# stm_board_f407_1_2_4.net
KiCad netlist of a schematic drawn in EAGLE
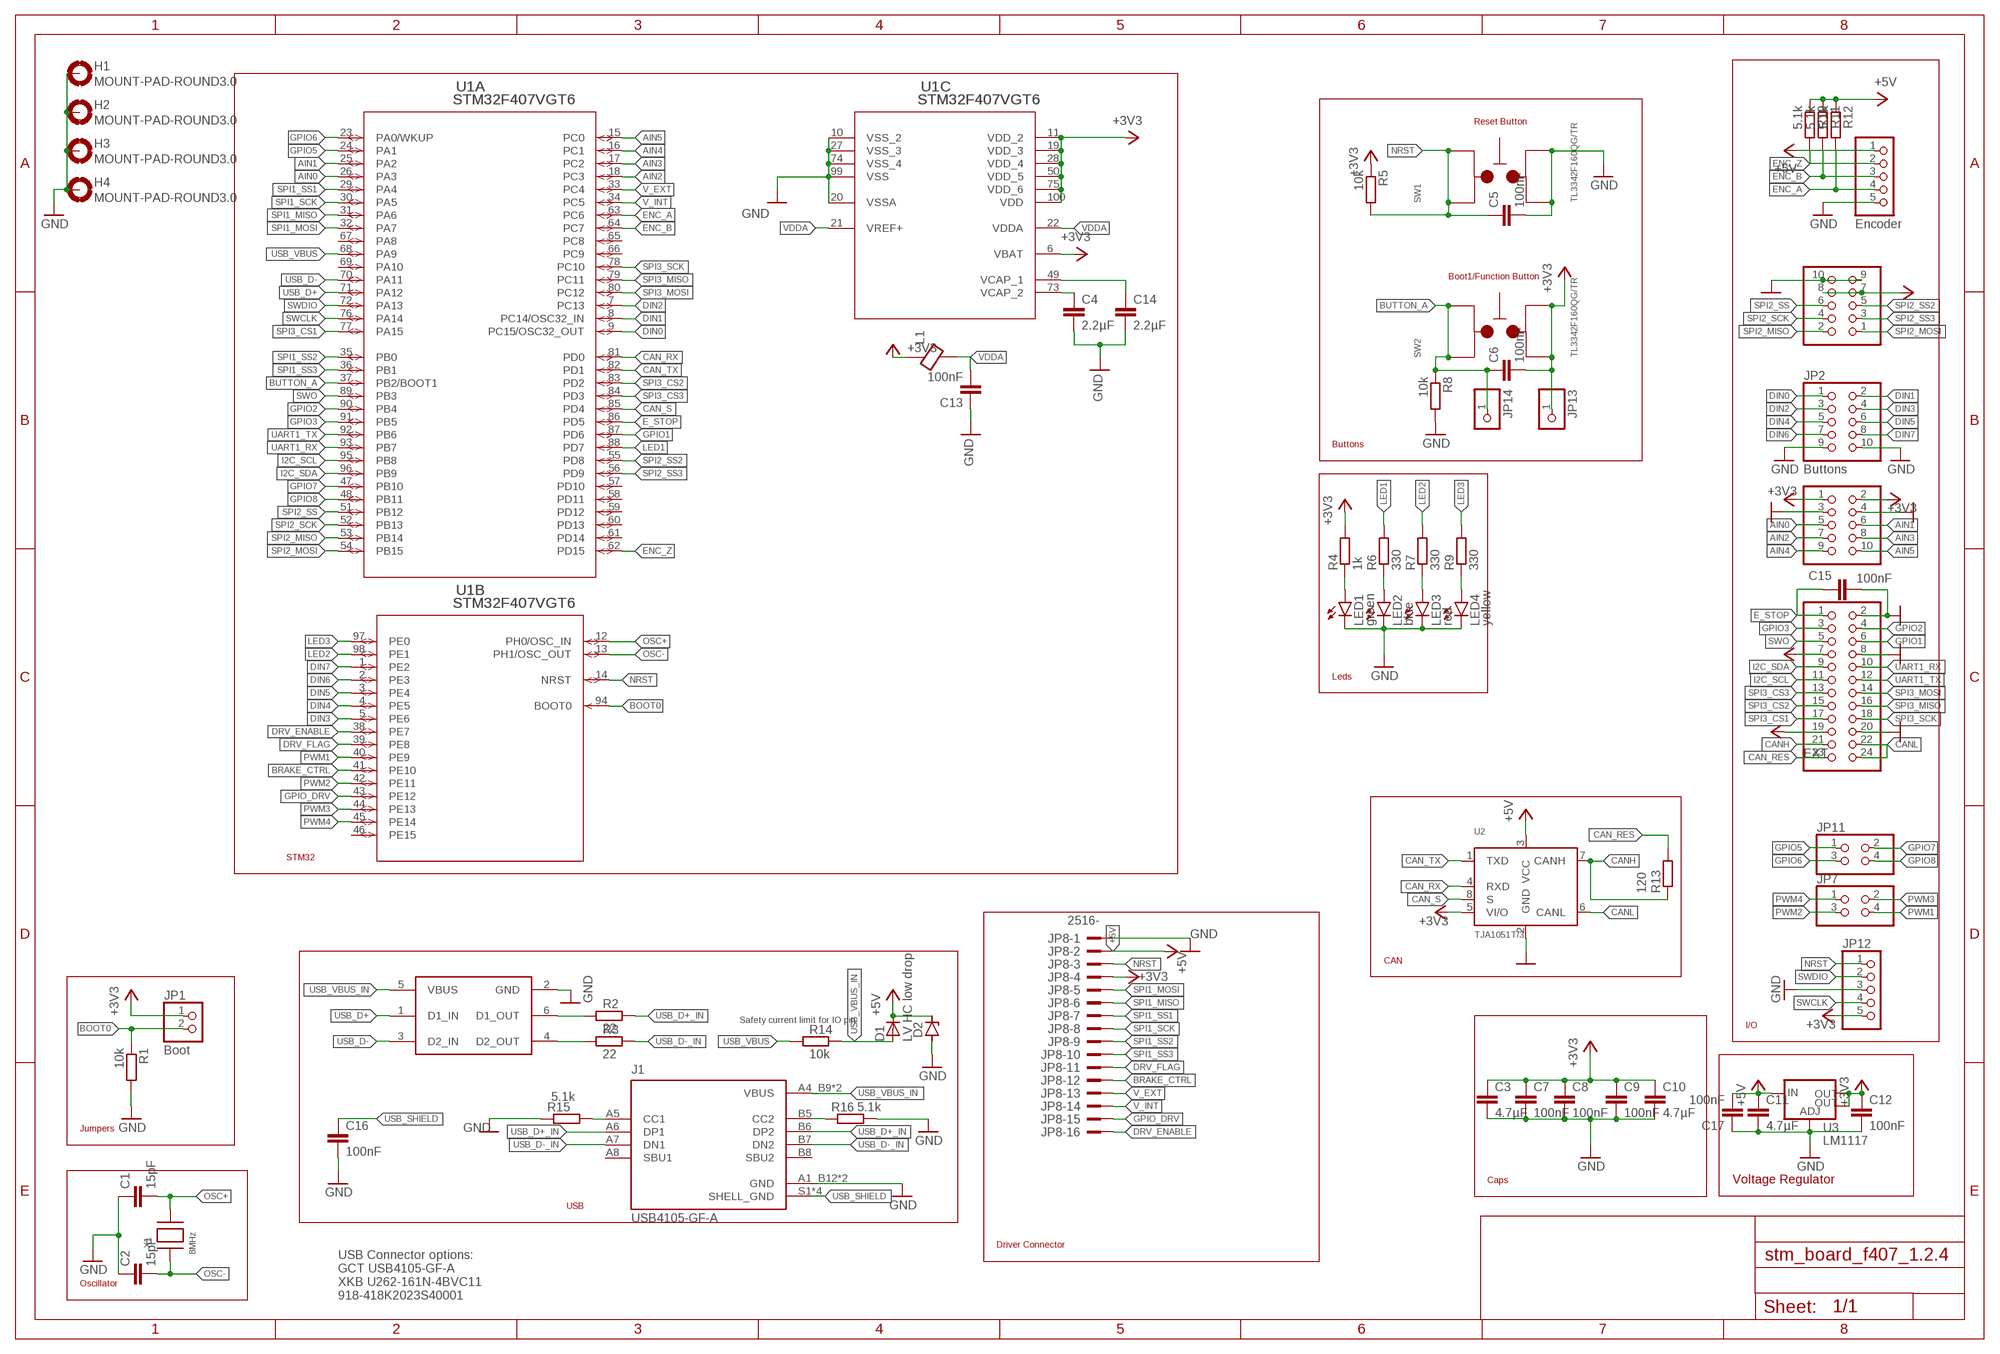
[diagram p0: schematic, sheet 1]

(export (version "E")
  (design (tool "Eeschema 10.0.6"))
  (components
    (comp (ref "C1")
      (value "15pF")
      (footprint "eagle-import:C0603")
      (libsource (lib "eagle-import") (part "C-EUC0603"))
    )
    (comp (ref "C2")
      (value "15pF")
      (footprint "eagle-import:C0603")
      (libsource (lib "eagle-import") (part "C-EUC0603"))
    )
    (comp (ref "C3")
      (value "4.7µF")
      (footprint "eagle-import:C0805")
      (libsource (lib "eagle-import") (part "C-EUC0805"))
    )
    (comp (ref "C4")
      (value "2.2µF")
      (footprint "eagle-import:C0603")
      (libsource (lib "eagle-import") (part "C-EUC0603"))
    )
    (comp (ref "C5")
      (value "100nF")
      (footprint "eagle-import:C0603")
      (libsource (lib "eagle-import") (part "C-EUC0603"))
    )
    (comp (ref "C6")
      (value "100nF")
      (footprint "eagle-import:C0603")
      (libsource (lib "eagle-import") (part "C-EUC0603"))
    )
    (comp (ref "C7")
      (value "100nF")
      (footprint "eagle-import:C0603")
      (libsource (lib "eagle-import") (part "C-EUC0603"))
    )
    (comp (ref "C8")
      (value "100nF")
      (footprint "eagle-import:C0603")
      (libsource (lib "eagle-import") (part "C-EUC0603"))
    )
    (comp (ref "C9")
      (value "100nF")
      (footprint "eagle-import:C0603")
      (libsource (lib "eagle-import") (part "C-EUC0603"))
    )
    (comp (ref "C10")
      (value "4.7µF")
      (footprint "eagle-import:C0805")
      (libsource (lib "eagle-import") (part "C-EUC0805"))
    )
    (comp (ref "C11")
      (value "4.7µF")
      (footprint "eagle-import:C0805")
      (libsource (lib "eagle-import") (part "C-EUC0805"))
    )
    (comp (ref "C12")
      (value "100nF")
      (footprint "eagle-import:C0603")
      (libsource (lib "eagle-import") (part "C-EUC0603"))
    )
    (comp (ref "C13")
      (value "100nF")
      (footprint "eagle-import:C0603")
      (libsource (lib "eagle-import") (part "C-EUC0603"))
    )
    (comp (ref "C14")
      (value "2.2µF")
      (footprint "eagle-import:C0603")
      (libsource (lib "eagle-import") (part "C-EUC0603"))
    )
    (comp (ref "C15")
      (value "100nF")
      (footprint "eagle-import:C0603")
      (libsource (lib "eagle-import") (part "C-EUC0603"))
    )
    (comp (ref "C16")
      (value "100nF")
      (footprint "eagle-import:C0603")
      (libsource (lib "eagle-import") (part "C-EUC0603"))
    )
    (comp (ref "C17")
      (value "100nF")
      (footprint "eagle-import:C0603")
      (libsource (lib "eagle-import") (part "C-EUC0603"))
    )
    (comp (ref "D1")
      (value "LV HC low drop")
      (footprint "eagle-import:SMADIODE")
      (libsource (lib "eagle-import") (part "DIODESMA"))
    )
    (comp (ref "D2")
      (value "ZENER-DIODESOD80C")
      (footprint "eagle-import:SOD80C")
      (libsource (lib "eagle-import") (part "ZENER-DIODESOD80C"))
    )
    (comp (ref "H1")
      (value "MOUNT-PAD-ROUND3.0")
      (footprint "eagle-import:3,0-PAD")
      (libsource (lib "eagle-import") (part "MOUNT-PAD-ROUND3.0"))
    )
    (comp (ref "H2")
      (value "MOUNT-PAD-ROUND3.0")
      (footprint "eagle-import:3,0-PAD")
      (libsource (lib "eagle-import") (part "MOUNT-PAD-ROUND3.0"))
    )
    (comp (ref "H3")
      (value "MOUNT-PAD-ROUND3.0")
      (footprint "eagle-import:3,0-PAD")
      (libsource (lib "eagle-import") (part "MOUNT-PAD-ROUND3.0"))
    )
    (comp (ref "H4")
      (value "MOUNT-PAD-ROUND3.0")
      (footprint "eagle-import:3,0-PAD")
      (libsource (lib "eagle-import") (part "MOUNT-PAD-ROUND3.0"))
    )
    (comp (ref "J1")
      (value "USB4105-GF-A")
      (footprint "eagle-import:GCT_USB4105-GF-A")
      (fields (field (name "MF") "GCT"))
      (libsource (lib "eagle-import") (part "USB4105-GF-A"))
    )
    (comp (ref "JP1")
      (value "Boot")
      (footprint "eagle-import:1X02")
      (libsource (lib "eagle-import") (part "PINHD-1X2"))
    )
    (comp (ref "JP2")
      (value "Buttons")
      (footprint "eagle-import:2X05")
      (libsource (lib "eagle-import") (part "PINHD-2X5"))
    )
    (comp (ref "JP3")
      (value "Analog")
      (footprint "eagle-import:2X05")
      (libsource (lib "eagle-import") (part "PINHD-2X5"))
    )
    (comp (ref "JP4")
      (value "EXT")
      (footprint "eagle-import:2X12")
      (libsource (lib "eagle-import") (part "PINHD-2X12"))
    )
    (comp (ref "JP5")
      (value "Encoder")
      (footprint "eagle-import:1X05")
      (libsource (lib "eagle-import") (part "PINHD-1X5"))
    )
    (comp (ref "JP6")
      (value "SPI")
      (footprint "eagle-import:2X05")
      (libsource (lib "eagle-import") (part "PINHD-2X5"))
    )
    (comp (ref "JP7")
      (value "PINHD-2X2")
      (footprint "eagle-import:2X02")
      (libsource (lib "eagle-import") (part "PINHD-2X2"))
    )
    (comp (ref "JP8")
      (value "2516-")
      (footprint "eagle-import:PAK100_2500-16")
      (libsource (lib "eagle-import") (part "2516-"))
    )
    (comp (ref "JP11")
      (value "PINHD-2X2")
      (footprint "eagle-import:2X02")
      (libsource (lib "eagle-import") (part "PINHD-2X2"))
    )
    (comp (ref "JP12")
      (value "PINHD-1X5")
      (footprint "eagle-import:1X05")
      (libsource (lib "eagle-import") (part "PINHD-1X5"))
    )
    (comp (ref "JP13")
      (value "PINHD-1X1")
      (footprint "eagle-import:1X01")
      (libsource (lib "eagle-import") (part "PINHD-1X1"))
    )
    (comp (ref "JP14")
      (value "PINHD-1X1")
      (footprint "eagle-import:1X01")
      (libsource (lib "eagle-import") (part "PINHD-1X1"))
    )
    (comp (ref "L1")
      (value "GZ2012D601TF")
      (footprint "eagle-import:BLM21PG331SN1D")
      (fields
        (field (name "DIGIKEY_PART_NUMBER") "490-5988-2-ND")
        (field (name "MANUFACTURER") "Murata Electronics North America")
        (field (name "MPN") "BLM21PG331SN1D")
        (field (name "CREATED_BY") "PCBLayout.com")
      )
      (libsource (lib "eagle-import") (part "BLM21PG331SN1D"))
    )
    (comp (ref "LED1")
      (value "green")
      (footprint "eagle-import:SML0805")
      (libsource (lib "eagle-import") (part "LEDSML0805"))
    )
    (comp (ref "LED2")
      (value "blue")
      (footprint "eagle-import:SML0805")
      (libsource (lib "eagle-import") (part "LEDSML0805"))
    )
    (comp (ref "LED3")
      (value "red")
      (footprint "eagle-import:SML0805")
      (libsource (lib "eagle-import") (part "LEDSML0805"))
    )
    (comp (ref "LED4")
      (value "yellow")
      (footprint "eagle-import:SML0805")
      (libsource (lib "eagle-import") (part "LEDSML0805"))
    )
    (comp (ref "R1")
      (value "10k")
      (footprint "eagle-import:R0603")
      (libsource (lib "eagle-import") (part "R-EU_R0603"))
    )
    (comp (ref "R2")
      (value "22")
      (footprint "eagle-import:R0603")
      (libsource (lib "eagle-import") (part "R-EU_R0603"))
    )
    (comp (ref "R3")
      (value "22")
      (footprint "eagle-import:R0603")
      (libsource (lib "eagle-import") (part "R-EU_R0603"))
    )
    (comp (ref "R4")
      (value "1k")
      (footprint "eagle-import:R0603")
      (libsource (lib "eagle-import") (part "R-EU_R0603"))
    )
    (comp (ref "R5")
      (value "10k")
      (footprint "eagle-import:R0603")
      (libsource (lib "eagle-import") (part "R-EU_R0603"))
    )
    (comp (ref "R6")
      (value "330")
      (footprint "eagle-import:R0603")
      (libsource (lib "eagle-import") (part "R-EU_R0603"))
    )
    (comp (ref "R7")
      (value "330")
      (footprint "eagle-import:R0603")
      (libsource (lib "eagle-import") (part "R-EU_R0603"))
    )
    (comp (ref "R8")
      (value "10k")
      (footprint "eagle-import:R0603")
      (libsource (lib "eagle-import") (part "R-EU_R0603"))
    )
    (comp (ref "R9")
      (value "330")
      (footprint "eagle-import:R0603")
      (libsource (lib "eagle-import") (part "R-EU_R0603"))
    )
    (comp (ref "R10")
      (value "5.1k")
      (footprint "eagle-import:R0603")
      (libsource (lib "eagle-import") (part "R-EU_R0603"))
    )
    (comp (ref "R11")
      (value "5.1k")
      (footprint "eagle-import:R0603")
      (libsource (lib "eagle-import") (part "R-EU_R0603"))
    )
    (comp (ref "R12")
      (value "5.1k")
      (footprint "eagle-import:R0603")
      (libsource (lib "eagle-import") (part "R-EU_R0603"))
    )
    (comp (ref "R13")
      (value "120")
      (footprint "eagle-import:R0603")
      (libsource (lib "eagle-import") (part "R-EU_R0603"))
    )
    (comp (ref "R14")
      (value "10k")
      (footprint "eagle-import:R0603")
      (libsource (lib "eagle-import") (part "R-EU_R0603"))
    )
    (comp (ref "R15")
      (value "5.1k")
      (footprint "eagle-import:R0603")
      (libsource (lib "eagle-import") (part "R-EU_R0603"))
    )
    (comp (ref "R16")
      (value "5.1k")
      (footprint "eagle-import:R0603")
      (libsource (lib "eagle-import") (part "R-EU_R0603"))
    )
    (comp (ref "SW1")
      (value "TL3342F160QG/TR")
      (footprint "eagle-import:TL3342F160QG_TR")
      (fields
        (field (name "DIGI_KEY_PART_NUMBER") "EG2531CT-ND")
        (field (name "MANUFACTURER") "E-Switch")
        (field (name "CREATED_BY") "PCBLayout.com")
      )
      (libsource (lib "eagle-import") (part "TL3342F160QG/TR"))
    )
    (comp (ref "SW2")
      (value "TL3342F160QG/TR")
      (footprint "eagle-import:TL3342F160QG_TR")
      (fields
        (field (name "DIGI_KEY_PART_NUMBER") "EG2531CT-ND")
        (field (name "MANUFACTURER") "E-Switch")
        (field (name "CREATED_BY") "PCBLayout.com")
      )
      (libsource (lib "eagle-import") (part "TL3342F160QG/TR"))
    )
    (comp (ref "U1")
      (value "STM32F407VGT6")
      (footprint "eagle-import:LQFP100-14X14MM")
      (fields (field (name "COPYRIGHT") "Copyright (C) 2018 Accelerated Designs. All rights reserved"))
      (libsource (lib "eagle-import") (part "STM32F407VGT6"))
    )
    (comp (ref "U2")
      (value "TJA1051T/3")
      (footprint "eagle-import:SOT96-1")
      (fields (field (name "MF") "NXP Semiconductors"))
      (libsource (lib "eagle-import") (part "TJA1051T/3"))
    )
    (comp (ref "U3")
      (value "LM1117")
      (footprint "eagle-import:SOT223")
      (libsource (lib "eagle-import") (part "V_REG_LM1117SOT223"))
    )
    (comp (ref "U4")
      (value "USBLC6-2SC6")
      (footprint "eagle-import:TSOT-23-6")
      (libsource (lib "eagle-import") (part "USBLC6-2SC6"))
    )
    (comp (ref "X1")
      (value "8MHz")
      (footprint "eagle-import:NX5032")
      (libsource (lib "eagle-import") (part "XTALNX5032"))
    )
  )
  (nets
    (net (code "1") (name "+3V3") (class "Default")
      (node (ref "C10") (pin "1") (pinfunction "1_1") (pintype "passive"))
      (node (ref "C12") (pin "1") (pinfunction "1_1") (pintype "passive"))
      (node (ref "C3") (pin "1") (pinfunction "1_1") (pintype "passive"))
      (node (ref "C6") (pin "2") (pinfunction "2_2") (pintype "passive"))
      (node (ref "C7") (pin "1") (pinfunction "1_1") (pintype "passive"))
      (node (ref "C8") (pin "1") (pinfunction "1_1") (pintype "passive"))
      (node (ref "C9") (pin "1") (pinfunction "1_1") (pintype "passive"))
      (node (ref "JP1") (pin "1") (pinfunction "1_1") (pintype "passive"))
      (node (ref "JP12") (pin "5") (pinfunction "5_5") (pintype "passive"))
      (node (ref "JP13") (pin "1") (pinfunction "1_1") (pintype "passive"))
      (node (ref "JP3") (pin "1") (pinfunction "1_1") (pintype "passive"))
      (node (ref "JP3") (pin "2") (pinfunction "2_2") (pintype "passive"))
      (node (ref "JP4") (pin "7") (pinfunction "7_7") (pintype "passive"))
      (node (ref "JP6") (pin "7") (pinfunction "7_7") (pintype "passive"))
      (node (ref "JP6") (pin "8") (pinfunction "8_8") (pintype "passive"))
      (node (ref "JP8") (pin "4") (pinfunction "KL_4") (pintype "passive"))
      (node (ref "L1") (pin "1") (pinfunction "1_1") (pintype "passive"))
      (node (ref "R4") (pin "2") (pinfunction "2_2") (pintype "passive"))
      (node (ref "R5") (pin "1") (pinfunction "1_1") (pintype "passive"))
      (node (ref "SW2") (pin "1") (pinfunction "1_1") (pintype "passive"))
      (node (ref "SW2") (pin "2") (pinfunction "2_2") (pintype "passive"))
      (node (ref "U1") (pin "100") (pinfunction "VDD_100") (pintype "power_in"))
      (node (ref "U1") (pin "11") (pinfunction "VDD_2_11") (pintype "power_in"))
      (node (ref "U1") (pin "19") (pinfunction "VDD_3_19") (pintype "power_in"))
      (node (ref "U1") (pin "28") (pinfunction "VDD_4_28") (pintype "power_in"))
      (node (ref "U1") (pin "50") (pinfunction "VDD_5_50") (pintype "power_in"))
      (node (ref "U1") (pin "6") (pinfunction "VBAT_6") (pintype "power_in"))
      (node (ref "U1") (pin "75") (pinfunction "VDD_6_75") (pintype "power_in"))
      (node (ref "U2") (pin "5") (pinfunction "VI/O_5") (pintype "passive"))
      (node (ref "U3") (pin "2") (pinfunction "OUT_2") (pintype "output"))
      (node (ref "U3") (pin "4") (pinfunction "OUT_4") (pintype "output"))
    )
    (net (code "2") (name "+5V") (class "Default")
      (node (ref "C11") (pin "1") (pinfunction "1_1") (pintype "passive"))
      (node (ref "C17") (pin "2") (pinfunction "2_2") (pintype "passive"))
      (node (ref "D1") (pin "C") (pinfunction "C_C") (pintype "passive"))
      (node (ref "D2") (pin "C") (pinfunction "C_C") (pintype "passive"))
      (node (ref "JP4") (pin "19") (pinfunction "19_19") (pintype "passive"))
      (node (ref "JP5") (pin "1") (pinfunction "1_1") (pintype "passive"))
      (node (ref "JP8") (pin "2") (pinfunction "KL_2") (pintype "passive"))
      (node (ref "R10") (pin "1") (pinfunction "1_1") (pintype "passive"))
      (node (ref "R11") (pin "1") (pinfunction "1_1") (pintype "passive"))
      (node (ref "R12") (pin "1") (pinfunction "1_1") (pintype "passive"))
      (node (ref "U2") (pin "3") (pinfunction "VCC_3") (pintype "bidirectional"))
      (node (ref "U3") (pin "3") (pinfunction "IN_3") (pintype "input"))
    )
    (net (code "3") (name "AIN0") (class "Default")
      (node (ref "JP3") (pin "5") (pinfunction "5_5") (pintype "passive"))
      (node (ref "U1") (pin "26") (pinfunction "PA3_26") (pintype "bidirectional"))
    )
    (net (code "4") (name "AIN1") (class "Default")
      (node (ref "JP3") (pin "6") (pinfunction "6_6") (pintype "passive"))
      (node (ref "U1") (pin "25") (pinfunction "PA2_25") (pintype "bidirectional"))
    )
    (net (code "5") (name "AIN2") (class "Default")
      (node (ref "JP3") (pin "7") (pinfunction "7_7") (pintype "passive"))
      (node (ref "U1") (pin "18") (pinfunction "PC3_18") (pintype "bidirectional"))
    )
    (net (code "6") (name "AIN3") (class "Default")
      (node (ref "JP3") (pin "8") (pinfunction "8_8") (pintype "passive"))
      (node (ref "U1") (pin "17") (pinfunction "PC2_17") (pintype "bidirectional"))
    )
    (net (code "7") (name "AIN4") (class "Default")
      (node (ref "JP3") (pin "9") (pinfunction "9_9") (pintype "passive"))
      (node (ref "U1") (pin "16") (pinfunction "PC1_16") (pintype "bidirectional"))
    )
    (net (code "8") (name "AIN5") (class "Default")
      (node (ref "JP3") (pin "10") (pinfunction "10_10") (pintype "passive"))
      (node (ref "U1") (pin "15") (pinfunction "PC0_15") (pintype "bidirectional"))
    )
    (net (code "9") (name "BOOT0") (class "Default")
      (node (ref "JP1") (pin "2") (pinfunction "2_2") (pintype "passive"))
      (node (ref "R1") (pin "1") (pinfunction "1_1") (pintype "passive"))
      (node (ref "U1") (pin "94") (pinfunction "BOOT0_94") (pintype "input"))
    )
    (net (code "10") (name "BRAKE_CTRL") (class "Default")
      (node (ref "JP8") (pin "12") (pinfunction "KL_12") (pintype "passive"))
      (node (ref "U1") (pin "41") (pinfunction "PE10_41") (pintype "bidirectional"))
    )
    (net (code "11") (name "BUTTON_A") (class "Default")
      (node (ref "C6") (pin "1") (pinfunction "1_1") (pintype "passive"))
      (node (ref "JP14") (pin "1") (pinfunction "1_1") (pintype "passive"))
      (node (ref "R8") (pin "1") (pinfunction "1_1") (pintype "passive"))
      (node (ref "SW2") (pin "3") (pinfunction "3_3") (pintype "passive"))
      (node (ref "SW2") (pin "4") (pinfunction "4_4") (pintype "passive"))
      (node (ref "U1") (pin "37") (pinfunction "PB2/BOOT1_37") (pintype "bidirectional"))
    )
    (net (code "12") (name "CANH") (class "Default")
      (node (ref "JP4") (pin "21") (pinfunction "21_21") (pintype "passive"))
      (node (ref "R13") (pin "1") (pinfunction "1_1") (pintype "passive"))
      (node (ref "U2") (pin "7") (pinfunction "CANH_7") (pintype "bidirectional"))
    )
    (net (code "13") (name "CANL") (class "Default")
      (node (ref "JP4") (pin "22") (pinfunction "22_22") (pintype "passive"))
      (node (ref "JP4") (pin "24") (pinfunction "24_24") (pintype "passive"))
      (node (ref "U2") (pin "6") (pinfunction "CANL_6") (pintype "bidirectional"))
    )
    (net (code "14") (name "CAN_RES") (class "Default")
      (node (ref "JP4") (pin "23") (pinfunction "23_23") (pintype "passive"))
      (node (ref "R13") (pin "2") (pinfunction "2_2") (pintype "passive"))
    )
    (net (code "15") (name "CAN_RX") (class "Default")
      (node (ref "U1") (pin "81") (pinfunction "PD0_81") (pintype "bidirectional"))
      (node (ref "U2") (pin "4") (pinfunction "RXD_4") (pintype "bidirectional"))
    )
    (net (code "16") (name "CAN_S") (class "Default")
      (node (ref "U1") (pin "85") (pinfunction "PD4_85") (pintype "bidirectional"))
      (node (ref "U2") (pin "8") (pinfunction "S_8") (pintype "power_in"))
    )
    (net (code "17") (name "CAN_TX") (class "Default")
      (node (ref "U1") (pin "82") (pinfunction "PD1_82") (pintype "bidirectional"))
      (node (ref "U2") (pin "1") (pinfunction "TXD_1") (pintype "output"))
    )
    (net (code "18") (name "DIN0") (class "Default")
      (node (ref "JP2") (pin "1") (pinfunction "1_1") (pintype "passive"))
      (node (ref "U1") (pin "9") (pinfunction "PC15/OSC32_OUT_9") (pintype "bidirectional"))
    )
    (net (code "19") (name "DIN1") (class "Default")
      (node (ref "JP2") (pin "2") (pinfunction "2_2") (pintype "passive"))
      (node (ref "U1") (pin "8") (pinfunction "PC14/OSC32_IN_8") (pintype "bidirectional"))
    )
    (net (code "20") (name "DIN2") (class "Default")
      (node (ref "JP2") (pin "3") (pinfunction "3_3") (pintype "passive"))
      (node (ref "U1") (pin "7") (pinfunction "PC13_7") (pintype "bidirectional"))
    )
    (net (code "21") (name "DIN3") (class "Default")
      (node (ref "JP2") (pin "4") (pinfunction "4_4") (pintype "passive"))
      (node (ref "U1") (pin "5") (pinfunction "PE6_5") (pintype "bidirectional"))
    )
    (net (code "22") (name "DIN4") (class "Default")
      (node (ref "JP2") (pin "5") (pinfunction "5_5") (pintype "passive"))
      (node (ref "U1") (pin "4") (pinfunction "PE5_4") (pintype "bidirectional"))
    )
    (net (code "23") (name "DIN5") (class "Default")
      (node (ref "JP2") (pin "6") (pinfunction "6_6") (pintype "passive"))
      (node (ref "U1") (pin "3") (pinfunction "PE4_3") (pintype "bidirectional"))
    )
    (net (code "24") (name "DIN6") (class "Default")
      (node (ref "JP2") (pin "7") (pinfunction "7_7") (pintype "passive"))
      (node (ref "U1") (pin "2") (pinfunction "PE3_2") (pintype "bidirectional"))
    )
    (net (code "25") (name "DIN7") (class "Default")
      (node (ref "JP2") (pin "8") (pinfunction "8_8") (pintype "passive"))
      (node (ref "U1") (pin "1") (pinfunction "PE2_1") (pintype "bidirectional"))
    )
    (net (code "26") (name "DRV_ENABLE") (class "Default")
      (node (ref "JP8") (pin "16") (pinfunction "KL_16") (pintype "passive"))
      (node (ref "U1") (pin "38") (pinfunction "PE7_38") (pintype "bidirectional"))
    )
    (net (code "27") (name "DRV_FLAG") (class "Default")
      (node (ref "JP8") (pin "11") (pinfunction "KL_11") (pintype "passive"))
      (node (ref "U1") (pin "39") (pinfunction "PE8_39") (pintype "bidirectional"))
    )
    (net (code "28") (name "ENC_A") (class "Default")
      (node (ref "JP5") (pin "4") (pinfunction "4_4") (pintype "passive"))
      (node (ref "R12") (pin "2") (pinfunction "2_2") (pintype "passive"))
      (node (ref "U1") (pin "63") (pinfunction "PC6_63") (pintype "bidirectional"))
    )
    (net (code "29") (name "ENC_B") (class "Default")
      (node (ref "JP5") (pin "3") (pinfunction "3_3") (pintype "passive"))
      (node (ref "R11") (pin "2") (pinfunction "2_2") (pintype "passive"))
      (node (ref "U1") (pin "64") (pinfunction "PC7_64") (pintype "bidirectional"))
    )
    (net (code "30") (name "ENC_Z") (class "Default")
      (node (ref "JP5") (pin "2") (pinfunction "2_2") (pintype "passive"))
      (node (ref "R10") (pin "2") (pinfunction "2_2") (pintype "passive"))
      (node (ref "U1") (pin "62") (pinfunction "PD15_62") (pintype "bidirectional"))
    )
    (net (code "31") (name "E_STOP") (class "Default")
      (node (ref "C15") (pin "1") (pinfunction "1_1") (pintype "passive"))
      (node (ref "JP4") (pin "1") (pinfunction "1_1") (pintype "passive"))
      (node (ref "U1") (pin "86") (pinfunction "PD5_86") (pintype "bidirectional"))
    )
    (net (code "32") (name "GND") (class "Default")
      (node (ref "C1") (pin "1") (pinfunction "1_1") (pintype "passive"))
      (node (ref "C10") (pin "2") (pinfunction "2_2") (pintype "passive"))
      (node (ref "C11") (pin "2") (pinfunction "2_2") (pintype "passive"))
      (node (ref "C12") (pin "2") (pinfunction "2_2") (pintype "passive"))
      (node (ref "C13") (pin "1") (pinfunction "1_1") (pintype "passive"))
      (node (ref "C14") (pin "2") (pinfunction "2_2") (pintype "passive"))
      (node (ref "C15") (pin "2") (pinfunction "2_2") (pintype "passive"))
      (node (ref "C16") (pin "2") (pinfunction "2_2") (pintype "passive"))
      (node (ref "C17") (pin "1") (pinfunction "1_1") (pintype "passive"))
      (node (ref "C2") (pin "1") (pinfunction "1_1") (pintype "passive"))
      (node (ref "C3") (pin "2") (pinfunction "2_2") (pintype "passive"))
      (node (ref "C4") (pin "2") (pinfunction "2_2") (pintype "passive"))
      (node (ref "C5") (pin "2") (pinfunction "2_2") (pintype "passive"))
      (node (ref "C7") (pin "2") (pinfunction "2_2") (pintype "passive"))
      (node (ref "C8") (pin "2") (pinfunction "2_2") (pintype "passive"))
      (node (ref "C9") (pin "2") (pinfunction "2_2") (pintype "passive"))
      (node (ref "D2") (pin "A") (pinfunction "A_A") (pintype "passive"))
      (node (ref "H1") (pin "B3,0") (pinfunction "MOUNT_B3,0") (pintype "passive"))
      (node (ref "H2") (pin "B3,0") (pinfunction "MOUNT_B3,0") (pintype "passive"))
      (node (ref "H3") (pin "B3,0") (pinfunction "MOUNT_B3,0") (pintype "passive"))
      (node (ref "H4") (pin "B3,0") (pinfunction "MOUNT_B3,0") (pintype "passive"))
      (node (ref "J1") (pin "A1_B12") (pinfunction "GND_A1_B12") (pintype "power_in"))
      (node (ref "J1") (pin "B1_A12") (pinfunction "GND_B1_A12") (pintype "power_in"))
      (node (ref "JP12") (pin "3") (pinfunction "3_3") (pintype "passive"))
      (node (ref "JP2") (pin "10") (pinfunction "10_10") (pintype "passive"))
      (node (ref "JP2") (pin "9") (pinfunction "9_9") (pintype "passive"))
      (node (ref "JP3") (pin "3") (pinfunction "3_3") (pintype "passive"))
      (node (ref "JP3") (pin "4") (pinfunction "4_4") (pintype "passive"))
      (node (ref "JP4") (pin "2") (pinfunction "2_2") (pintype "passive"))
      (node (ref "JP4") (pin "20") (pinfunction "20_20") (pintype "passive"))
      (node (ref "JP4") (pin "8") (pinfunction "8_8") (pintype "passive"))
      (node (ref "JP5") (pin "5") (pinfunction "5_5") (pintype "passive"))
      (node (ref "JP6") (pin "10") (pinfunction "10_10") (pintype "passive"))
      (node (ref "JP6") (pin "9") (pinfunction "9_9") (pintype "passive"))
      (node (ref "JP8") (pin "1") (pinfunction "KL_1") (pintype "passive"))
      (node (ref "LED1") (pin "C") (pinfunction "C_C") (pintype "passive"))
      (node (ref "LED2") (pin "C") (pinfunction "C_C") (pintype "passive"))
      (node (ref "LED3") (pin "C") (pinfunction "C_C") (pintype "passive"))
      (node (ref "LED4") (pin "C") (pinfunction "C_C") (pintype "passive"))
      (node (ref "R1") (pin "2") (pinfunction "2_2") (pintype "passive"))
      (node (ref "R15") (pin "1") (pinfunction "1_1") (pintype "passive"))
      (node (ref "R16") (pin "2") (pinfunction "2_2") (pintype "passive"))
      (node (ref "R8") (pin "2") (pinfunction "2_2") (pintype "passive"))
      (node (ref "SW1") (pin "1") (pinfunction "1_1") (pintype "passive"))
      (node (ref "SW1") (pin "2") (pinfunction "2_2") (pintype "passive"))
      (node (ref "U1") (pin "10") (pinfunction "VSS_2_10") (pintype "power_in"))
      (node (ref "U1") (pin "20") (pinfunction "VSSA_20") (pintype "power_in"))
      (node (ref "U1") (pin "27") (pinfunction "VSS_3_27") (pintype "power_in"))
      (node (ref "U1") (pin "74") (pinfunction "VSS_4_74") (pintype "power_in"))
      (node (ref "U1") (pin "99") (pinfunction "VSS_99") (pintype "power_in"))
      (node (ref "U2") (pin "2") (pinfunction "GND_2") (pintype "bidirectional"))
      (node (ref "U3") (pin "1") (pinfunction "ADJ_1") (pintype "input"))
      (node (ref "U4") (pin "2") (pinfunction "GND_2") (pintype "bidirectional"))
    )
    (net (code "33") (name "GPIO1") (class "Default")
      (node (ref "JP4") (pin "6") (pinfunction "6_6") (pintype "passive"))
      (node (ref "U1") (pin "87") (pinfunction "PD6_87") (pintype "bidirectional"))
    )
    (net (code "34") (name "GPIO2") (class "Default")
      (node (ref "JP4") (pin "4") (pinfunction "4_4") (pintype "passive"))
      (node (ref "U1") (pin "90") (pinfunction "PB4_90") (pintype "bidirectional"))
    )
    (net (code "35") (name "GPIO3") (class "Default")
      (node (ref "JP4") (pin "3") (pinfunction "3_3") (pintype "passive"))
      (node (ref "U1") (pin "91") (pinfunction "PB5_91") (pintype "bidirectional"))
    )
    (net (code "36") (name "GPIO5") (class "Default")
      (node (ref "JP11") (pin "1") (pinfunction "1_1") (pintype "passive"))
      (node (ref "U1") (pin "24") (pinfunction "PA1_24") (pintype "bidirectional"))
    )
    (net (code "37") (name "GPIO6") (class "Default")
      (node (ref "JP11") (pin "3") (pinfunction "3_3") (pintype "passive"))
      (node (ref "U1") (pin "23") (pinfunction "PA0/WKUP_23") (pintype "bidirectional"))
    )
    (net (code "38") (name "GPIO7") (class "Default")
      (node (ref "JP11") (pin "2") (pinfunction "2_2") (pintype "passive"))
      (node (ref "U1") (pin "47") (pinfunction "PB10_47") (pintype "bidirectional"))
    )
    (net (code "39") (name "GPIO8") (class "Default")
      (node (ref "JP11") (pin "4") (pinfunction "4_4") (pintype "passive"))
      (node (ref "U1") (pin "48") (pinfunction "PB11_48") (pintype "bidirectional"))
    )
    (net (code "40") (name "GPIO_DRV") (class "Default")
      (node (ref "JP8") (pin "15") (pinfunction "KL_15") (pintype "passive"))
      (node (ref "U1") (pin "43") (pinfunction "PE12_43") (pintype "bidirectional"))
    )
    (net (code "41") (name "I2C_SCL") (class "Default")
      (node (ref "JP4") (pin "11") (pinfunction "11_11") (pintype "passive"))
      (node (ref "U1") (pin "95") (pinfunction "PB8_95") (pintype "bidirectional"))
    )
    (net (code "42") (name "I2C_SDA") (class "Default")
      (node (ref "JP4") (pin "9") (pinfunction "9_9") (pintype "passive"))
      (node (ref "U1") (pin "96") (pinfunction "PB9_96") (pintype "bidirectional"))
    )
    (net (code "43") (name "LED1") (class "Default")
      (node (ref "R6") (pin "2") (pinfunction "2_2") (pintype "passive"))
      (node (ref "U1") (pin "88") (pinfunction "PD7_88") (pintype "bidirectional"))
    )
    (net (code "44") (name "LED2") (class "Default")
      (node (ref "R7") (pin "2") (pinfunction "2_2") (pintype "passive"))
      (node (ref "U1") (pin "98") (pinfunction "PE1_98") (pintype "bidirectional"))
    )
    (net (code "45") (name "LED3") (class "Default")
      (node (ref "R9") (pin "2") (pinfunction "2_2") (pintype "passive"))
      (node (ref "U1") (pin "97") (pinfunction "PE0_97") (pintype "bidirectional"))
    )
    (net (code "46") (name "NRST") (class "Default")
      (node (ref "C5") (pin "1") (pinfunction "1_1") (pintype "passive"))
      (node (ref "JP12") (pin "1") (pinfunction "1_1") (pintype "passive"))
      (node (ref "JP8") (pin "3") (pinfunction "KL_3") (pintype "passive"))
      (node (ref "R5") (pin "2") (pinfunction "2_2") (pintype "passive"))
      (node (ref "SW1") (pin "3") (pinfunction "3_3") (pintype "passive"))
      (node (ref "SW1") (pin "4") (pinfunction "4_4") (pintype "passive"))
      (node (ref "U1") (pin "14") (pinfunction "NRST_14") (pintype "bidirectional"))
    )
    (net (code "47") (name "Net-(J1-CC1)") (class "Default")
      (node (ref "J1") (pin "A5") (pinfunction "CC1_A5") (pintype "bidirectional"))
      (node (ref "R15") (pin "2") (pinfunction "2_2") (pintype "passive"))
    )
    (net (code "48") (name "Net-(J1-CC2)") (class "Default")
      (node (ref "J1") (pin "B5") (pinfunction "CC2_B5") (pintype "bidirectional"))
      (node (ref "R16") (pin "1") (pinfunction "1_1") (pintype "passive"))
    )
    (net (code "49") (name "Net-(LED1-PadA)") (class "Default")
      (node (ref "LED1") (pin "A") (pinfunction "A_A") (pintype "passive"))
      (node (ref "R4") (pin "1") (pinfunction "1_1") (pintype "passive"))
    )
    (net (code "50") (name "Net-(LED2-PadA)") (class "Default")
      (node (ref "LED2") (pin "A") (pinfunction "A_A") (pintype "passive"))
      (node (ref "R6") (pin "1") (pinfunction "1_1") (pintype "passive"))
    )
    (net (code "51") (name "Net-(LED3-PadA)") (class "Default")
      (node (ref "LED3") (pin "A") (pinfunction "A_A") (pintype "passive"))
      (node (ref "R7") (pin "1") (pinfunction "1_1") (pintype "passive"))
    )
    (net (code "52") (name "Net-(LED4-PadA)") (class "Default")
      (node (ref "LED4") (pin "A") (pinfunction "A_A") (pintype "passive"))
      (node (ref "R9") (pin "1") (pinfunction "1_1") (pintype "passive"))
    )
    (net (code "53") (name "Net-(U1C-VCAP_1)") (class "Default")
      (node (ref "C14") (pin "1") (pinfunction "1_1") (pintype "passive"))
      (node (ref "U1") (pin "49") (pinfunction "VCAP_1_49") (pintype "power_in"))
    )
    (net (code "54") (name "Net-(U1C-VCAP_2)") (class "Default")
      (node (ref "C4") (pin "1") (pinfunction "1_1") (pintype "passive"))
      (node (ref "U1") (pin "73") (pinfunction "VCAP_2_73") (pintype "power_in"))
    )
    (net (code "55") (name "Net-(U4-D1_OUT)") (class "Default")
      (node (ref "R2") (pin "1") (pinfunction "1_1") (pintype "passive"))
      (node (ref "U4") (pin "6") (pinfunction "D1_OUT_6") (pintype "bidirectional"))
    )
    (net (code "56") (name "Net-(U4-D2_OUT)") (class "Default")
      (node (ref "R3") (pin "1") (pinfunction "1_1") (pintype "passive"))
      (node (ref "U4") (pin "4") (pinfunction "D2_OUT_4") (pintype "bidirectional"))
    )
    (net (code "57") (name "OSC+") (class "Default")
      (node (ref "C1") (pin "2") (pinfunction "2_2") (pintype "passive"))
      (node (ref "U1") (pin "12") (pinfunction "PH0/OSC_IN_12") (pintype "bidirectional"))
      (node (ref "X1") (pin "P$2") (pinfunction "P$2_P$2") (pintype "bidirectional"))
    )
    (net (code "58") (name "OSC-") (class "Default")
      (node (ref "C2") (pin "2") (pinfunction "2_2") (pintype "passive"))
      (node (ref "U1") (pin "13") (pinfunction "PH1/OSC_OUT_13") (pintype "bidirectional"))
      (node (ref "X1") (pin "P$1") (pinfunction "P$1_P$1") (pintype "bidirectional"))
    )
    (net (code "59") (name "PWM1") (class "Default")
      (node (ref "JP7") (pin "4") (pinfunction "4_4") (pintype "passive"))
      (node (ref "U1") (pin "40") (pinfunction "PE9_40") (pintype "bidirectional"))
    )
    (net (code "60") (name "PWM2") (class "Default")
      (node (ref "JP7") (pin "3") (pinfunction "3_3") (pintype "passive"))
      (node (ref "U1") (pin "42") (pinfunction "PE11_42") (pintype "bidirectional"))
    )
    (net (code "61") (name "PWM3") (class "Default")
      (node (ref "JP7") (pin "2") (pinfunction "2_2") (pintype "passive"))
      (node (ref "U1") (pin "44") (pinfunction "PE13_44") (pintype "bidirectional"))
    )
    (net (code "62") (name "PWM4") (class "Default")
      (node (ref "JP7") (pin "1") (pinfunction "1_1") (pintype "passive"))
      (node (ref "U1") (pin "45") (pinfunction "PE14_45") (pintype "bidirectional"))
    )
    (net (code "63") (name "SPI1_MISO") (class "Default")
      (node (ref "JP8") (pin "6") (pinfunction "KL_6") (pintype "passive"))
      (node (ref "U1") (pin "31") (pinfunction "PA6_31") (pintype "bidirectional"))
    )
    (net (code "64") (name "SPI1_MOSI") (class "Default")
      (node (ref "JP8") (pin "5") (pinfunction "KL_5") (pintype "passive"))
      (node (ref "U1") (pin "32") (pinfunction "PA7_32") (pintype "bidirectional"))
    )
    (net (code "65") (name "SPI1_SCK") (class "Default")
      (node (ref "JP8") (pin "8") (pinfunction "KL_8") (pintype "passive"))
      (node (ref "U1") (pin "30") (pinfunction "PA5_30") (pintype "bidirectional"))
    )
    (net (code "66") (name "SPI1_SS1") (class "Default")
      (node (ref "JP8") (pin "7") (pinfunction "KL_7") (pintype "passive"))
      (node (ref "U1") (pin "29") (pinfunction "PA4_29") (pintype "bidirectional"))
    )
    (net (code "67") (name "SPI1_SS2") (class "Default")
      (node (ref "JP8") (pin "9") (pinfunction "KL_9") (pintype "passive"))
      (node (ref "U1") (pin "35") (pinfunction "PB0_35") (pintype "bidirectional"))
    )
    (net (code "68") (name "SPI1_SS3") (class "Default")
      (node (ref "JP8") (pin "10") (pinfunction "KL_10") (pintype "passive"))
      (node (ref "U1") (pin "36") (pinfunction "PB1_36") (pintype "bidirectional"))
    )
    (net (code "69") (name "SPI2_MISO") (class "Default")
      (node (ref "JP6") (pin "2") (pinfunction "2_2") (pintype "passive"))
      (node (ref "U1") (pin "53") (pinfunction "PB14_53") (pintype "bidirectional"))
    )
    (net (code "70") (name "SPI2_MOSI") (class "Default")
      (node (ref "JP6") (pin "1") (pinfunction "1_1") (pintype "passive"))
      (node (ref "U1") (pin "54") (pinfunction "PB15_54") (pintype "bidirectional"))
    )
    (net (code "71") (name "SPI2_SCK") (class "Default")
      (node (ref "JP6") (pin "4") (pinfunction "4_4") (pintype "passive"))
      (node (ref "U1") (pin "52") (pinfunction "PB13_52") (pintype "bidirectional"))
    )
    (net (code "72") (name "SPI2_SS") (class "Default")
      (node (ref "JP6") (pin "6") (pinfunction "6_6") (pintype "passive"))
      (node (ref "U1") (pin "51") (pinfunction "PB12_51") (pintype "bidirectional"))
    )
    (net (code "73") (name "SPI2_SS2") (class "Default")
      (node (ref "JP6") (pin "5") (pinfunction "5_5") (pintype "passive"))
      (node (ref "U1") (pin "55") (pinfunction "PD8_55") (pintype "bidirectional"))
    )
    (net (code "74") (name "SPI2_SS3") (class "Default")
      (node (ref "JP6") (pin "3") (pinfunction "3_3") (pintype "passive"))
      (node (ref "U1") (pin "56") (pinfunction "PD9_56") (pintype "bidirectional"))
    )
    (net (code "75") (name "SPI3_CS1") (class "Default")
      (node (ref "JP4") (pin "17") (pinfunction "17_17") (pintype "passive"))
      (node (ref "U1") (pin "77") (pinfunction "PA15_77") (pintype "bidirectional"))
    )
    (net (code "76") (name "SPI3_CS2") (class "Default")
      (node (ref "JP4") (pin "15") (pinfunction "15_15") (pintype "passive"))
      (node (ref "U1") (pin "83") (pinfunction "PD2_83") (pintype "bidirectional"))
    )
    (net (code "77") (name "SPI3_CS3") (class "Default")
      (node (ref "JP4") (pin "13") (pinfunction "13_13") (pintype "passive"))
      (node (ref "U1") (pin "84") (pinfunction "PD3_84") (pintype "bidirectional"))
    )
    (net (code "78") (name "SPI3_MISO") (class "Default")
      (node (ref "JP4") (pin "16") (pinfunction "16_16") (pintype "passive"))
      (node (ref "U1") (pin "79") (pinfunction "PC11_79") (pintype "bidirectional"))
    )
    (net (code "79") (name "SPI3_MOSI") (class "Default")
      (node (ref "JP4") (pin "14") (pinfunction "14_14") (pintype "passive"))
      (node (ref "U1") (pin "80") (pinfunction "PC12_80") (pintype "bidirectional"))
    )
    (net (code "80") (name "SPI3_SCK") (class "Default")
      (node (ref "JP4") (pin "18") (pinfunction "18_18") (pintype "passive"))
      (node (ref "U1") (pin "78") (pinfunction "PC10_78") (pintype "bidirectional"))
    )
    (net (code "81") (name "SWCLK") (class "Default")
      (node (ref "JP12") (pin "4") (pinfunction "4_4") (pintype "passive"))
      (node (ref "U1") (pin "76") (pinfunction "PA14_76") (pintype "bidirectional"))
    )
    (net (code "82") (name "SWDIO") (class "Default")
      (node (ref "JP12") (pin "2") (pinfunction "2_2") (pintype "passive"))
      (node (ref "U1") (pin "72") (pinfunction "PA13_72") (pintype "bidirectional"))
    )
    (net (code "83") (name "SWO") (class "Default")
      (node (ref "JP4") (pin "5") (pinfunction "5_5") (pintype "passive"))
      (node (ref "U1") (pin "89") (pinfunction "PB3_89") (pintype "bidirectional"))
    )
    (net (code "84") (name "UART1_RX") (class "Default")
      (node (ref "JP4") (pin "10") (pinfunction "10_10") (pintype "passive"))
      (node (ref "U1") (pin "93") (pinfunction "PB7_93") (pintype "bidirectional"))
    )
    (net (code "85") (name "UART1_TX") (class "Default")
      (node (ref "JP4") (pin "12") (pinfunction "12_12") (pintype "passive"))
      (node (ref "U1") (pin "92") (pinfunction "PB6_92") (pintype "bidirectional"))
    )
    (net (code "86") (name "USB_D+") (class "Default")
      (node (ref "U1") (pin "71") (pinfunction "PA12_71") (pintype "bidirectional"))
      (node (ref "U4") (pin "1") (pinfunction "D1_IN_1") (pintype "bidirectional"))
    )
    (net (code "87") (name "USB_D+_IN") (class "Default")
      (node (ref "J1") (pin "A6") (pinfunction "DP1_A6") (pintype "bidirectional"))
      (node (ref "J1") (pin "B6") (pinfunction "DP2_B6") (pintype "bidirectional"))
      (node (ref "R2") (pin "2") (pinfunction "2_2") (pintype "passive"))
    )
    (net (code "88") (name "USB_D-") (class "Default")
      (node (ref "U1") (pin "70") (pinfunction "PA11_70") (pintype "bidirectional"))
      (node (ref "U4") (pin "3") (pinfunction "D2_IN_3") (pintype "bidirectional"))
    )
    (net (code "89") (name "USB_D-_IN") (class "Default")
      (node (ref "J1") (pin "A7") (pinfunction "DN1_A7") (pintype "bidirectional"))
      (node (ref "J1") (pin "B7") (pinfunction "DN2_B7") (pintype "bidirectional"))
      (node (ref "R3") (pin "2") (pinfunction "2_2") (pintype "passive"))
    )
    (net (code "90") (name "USB_SHIELD") (class "Default")
      (node (ref "C16") (pin "1") (pinfunction "1_1") (pintype "passive"))
      (node (ref "J1") (pin "S1") (pinfunction "SHELL_GND_S1") (pintype "power_in"))
      (node (ref "J1") (pin "S2") (pinfunction "SHELL_GND_S2") (pintype "power_in"))
      (node (ref "J1") (pin "S3") (pinfunction "SHELL_GND_S3") (pintype "power_in"))
      (node (ref "J1") (pin "S4") (pinfunction "SHELL_GND_S4") (pintype "power_in"))
    )
    (net (code "91") (name "USB_VBUS") (class "Default")
      (node (ref "R14") (pin "1") (pinfunction "1_1") (pintype "passive"))
      (node (ref "U1") (pin "68") (pinfunction "PA9_68") (pintype "bidirectional"))
    )
    (net (code "92") (name "USB_VBUS_IN") (class "Default")
      (node (ref "D1") (pin "A") (pinfunction "A_A") (pintype "passive"))
      (node (ref "J1") (pin "A4_B9") (pinfunction "VBUS_A4_B9") (pintype "power_in"))
      (node (ref "J1") (pin "B4_A9") (pinfunction "VBUS_B4_A9") (pintype "power_in"))
      (node (ref "R14") (pin "2") (pinfunction "2_2") (pintype "passive"))
      (node (ref "U4") (pin "5") (pinfunction "VBUS_5") (pintype "bidirectional"))
    )
    (net (code "93") (name "VDDA") (class "Default")
      (node (ref "C13") (pin "2") (pinfunction "2_2") (pintype "passive"))
      (node (ref "L1") (pin "2") (pinfunction "2_2") (pintype "passive"))
      (node (ref "U1") (pin "21") (pinfunction "VREF+_21") (pintype "power_in"))
      (node (ref "U1") (pin "22") (pinfunction "VDDA_22") (pintype "power_in"))
    )
    (net (code "94") (name "V_EXT") (class "Default")
      (node (ref "JP8") (pin "13") (pinfunction "KL_13") (pintype "passive"))
      (node (ref "U1") (pin "33") (pinfunction "PC4_33") (pintype "bidirectional"))
    )
    (net (code "95") (name "V_INT") (class "Default")
      (node (ref "JP8") (pin "14") (pinfunction "KL_14") (pintype "passive"))
      (node (ref "U1") (pin "34") (pinfunction "PC5_34") (pintype "bidirectional"))
    )
    (net (code "96") (name "unconnected-(J1-SBU1-PadA8)") (class "Default")
      (node (ref "J1") (pin "A8") (pinfunction "SBU1_A8") (pintype "bidirectional"))
    )
    (net (code "97") (name "unconnected-(J1-SBU2-PadB8)") (class "Default")
      (node (ref "J1") (pin "B8") (pinfunction "SBU2_B8") (pintype "bidirectional"))
    )
    (net (code "98") (name "unconnected-(U1A-PA8-Pad67)") (class "Default")
      (node (ref "U1") (pin "67") (pinfunction "PA8_67") (pintype "bidirectional"))
    )
    (net (code "99") (name "unconnected-(U1A-PA10-Pad69)") (class "Default")
      (node (ref "U1") (pin "69") (pinfunction "PA10_69") (pintype "bidirectional"))
    )
    (net (code "100") (name "unconnected-(U1A-PC8-Pad65)") (class "Default")
      (node (ref "U1") (pin "65") (pinfunction "PC8_65") (pintype "bidirectional"))
    )
    (net (code "101") (name "unconnected-(U1A-PC9-Pad66)") (class "Default")
      (node (ref "U1") (pin "66") (pinfunction "PC9_66") (pintype "bidirectional"))
    )
    (net (code "102") (name "unconnected-(U1A-PD10-Pad57)") (class "Default")
      (node (ref "U1") (pin "57") (pinfunction "PD10_57") (pintype "bidirectional"))
    )
    (net (code "103") (name "unconnected-(U1A-PD11-Pad58)") (class "Default")
      (node (ref "U1") (pin "58") (pinfunction "PD11_58") (pintype "bidirectional"))
    )
    (net (code "104") (name "unconnected-(U1A-PD12-Pad59)") (class "Default")
      (node (ref "U1") (pin "59") (pinfunction "PD12_59") (pintype "bidirectional"))
    )
    (net (code "105") (name "unconnected-(U1A-PD13-Pad60)") (class "Default")
      (node (ref "U1") (pin "60") (pinfunction "PD13_60") (pintype "bidirectional"))
    )
    (net (code "106") (name "unconnected-(U1A-PD14-Pad61)") (class "Default")
      (node (ref "U1") (pin "61") (pinfunction "PD14_61") (pintype "bidirectional"))
    )
    (net (code "107") (name "unconnected-(U1B-PE15-Pad46)") (class "Default")
      (node (ref "U1") (pin "46") (pinfunction "PE15_46") (pintype "bidirectional"))
    )
  )
)
